# powerdistribution.net
KiCad netlist of a schematic drawn in EAGLE
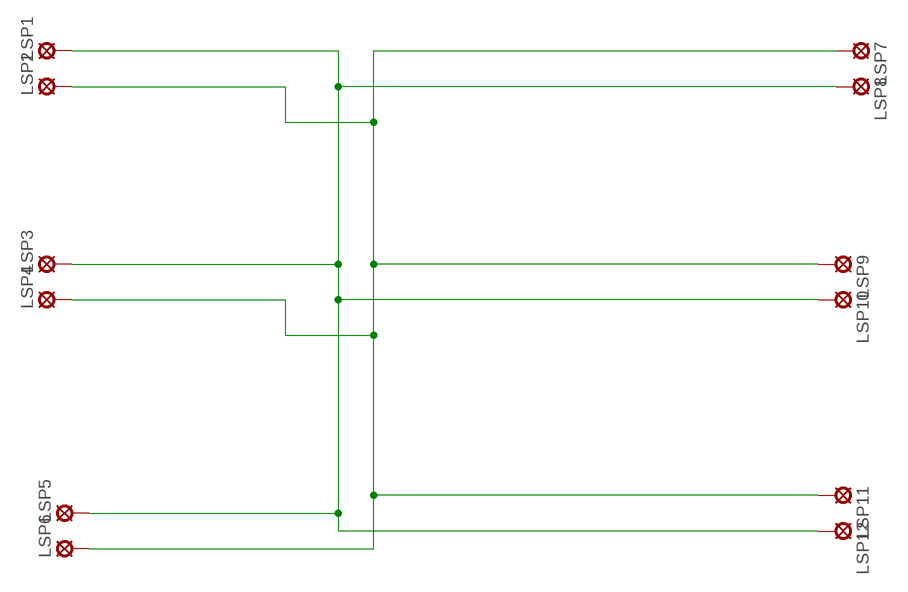
[diagram p0: schematic, sheet 1]

(export (version "E")
  (design (tool "Eeschema 10.0.6"))
  (components
    (comp (ref "LSP1")
      (value "SE11")
      (footprint "eagle-import:SE11")
      (libsource (lib "eagle-import") (part "SE11"))
    )
    (comp (ref "LSP2")
      (value "SE11")
      (footprint "eagle-import:SE11")
      (libsource (lib "eagle-import") (part "SE11"))
    )
    (comp (ref "LSP3")
      (value "SE11")
      (footprint "eagle-import:SE11")
      (libsource (lib "eagle-import") (part "SE11"))
    )
    (comp (ref "LSP4")
      (value "SE11")
      (footprint "eagle-import:SE11")
      (libsource (lib "eagle-import") (part "SE11"))
    )
    (comp (ref "LSP5")
      (value "SE11")
      (footprint "eagle-import:SE11")
      (libsource (lib "eagle-import") (part "SE11"))
    )
    (comp (ref "LSP6")
      (value "SE11")
      (footprint "eagle-import:SE11")
      (libsource (lib "eagle-import") (part "SE11"))
    )
    (comp (ref "LSP7")
      (value "SE11")
      (footprint "eagle-import:SE11")
      (libsource (lib "eagle-import") (part "SE11"))
    )
    (comp (ref "LSP8")
      (value "SE11")
      (footprint "eagle-import:SE11")
      (libsource (lib "eagle-import") (part "SE11"))
    )
    (comp (ref "LSP9")
      (value "SE11")
      (footprint "eagle-import:SE11")
      (libsource (lib "eagle-import") (part "SE11"))
    )
    (comp (ref "LSP10")
      (value "SE11")
      (footprint "eagle-import:SE11")
      (libsource (lib "eagle-import") (part "SE11"))
    )
    (comp (ref "LSP11")
      (value "SE11")
      (footprint "eagle-import:SE11")
      (libsource (lib "eagle-import") (part "SE11"))
    )
    (comp (ref "LSP12")
      (value "SE11")
      (footprint "eagle-import:SE11")
      (libsource (lib "eagle-import") (part "SE11"))
    )
  )
  (nets
    (net (code "1") (name "Net-(LSP1-PadMP)") (class "Default")
      (node (ref "LSP1") (pin "MP") (pinfunction "MP_MP") (pintype "passive"))
      (node (ref "LSP10") (pin "MP") (pinfunction "MP_MP") (pintype "passive"))
      (node (ref "LSP12") (pin "MP") (pinfunction "MP_MP") (pintype "passive"))
      (node (ref "LSP3") (pin "MP") (pinfunction "MP_MP") (pintype "passive"))
      (node (ref "LSP5") (pin "MP") (pinfunction "MP_MP") (pintype "passive"))
      (node (ref "LSP8") (pin "MP") (pinfunction "MP_MP") (pintype "passive"))
    )
    (net (code "2") (name "Net-(LSP11-PadMP)") (class "Default")
      (node (ref "LSP11") (pin "MP") (pinfunction "MP_MP") (pintype "passive"))
      (node (ref "LSP2") (pin "MP") (pinfunction "MP_MP") (pintype "passive"))
      (node (ref "LSP4") (pin "MP") (pinfunction "MP_MP") (pintype "passive"))
      (node (ref "LSP6") (pin "MP") (pinfunction "MP_MP") (pintype "passive"))
      (node (ref "LSP7") (pin "MP") (pinfunction "MP_MP") (pintype "passive"))
      (node (ref "LSP9") (pin "MP") (pinfunction "MP_MP") (pintype "passive"))
    )
  )
)
